# ESP32.net
KiCad netlist of a schematic drawn in EAGLE
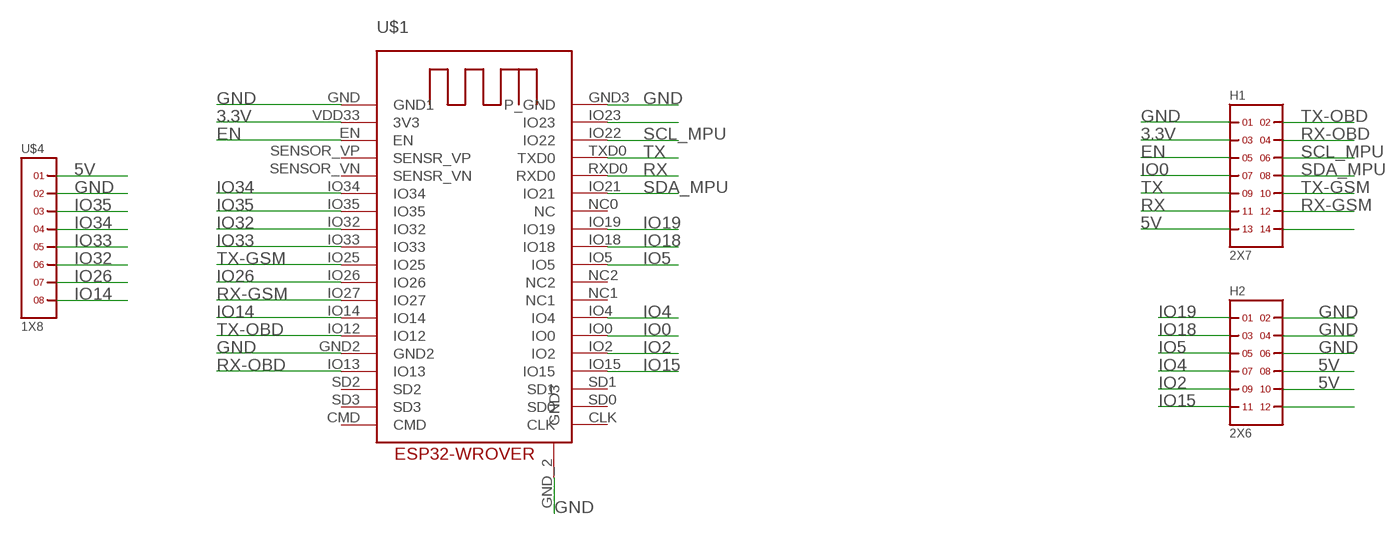
[diagram p0: schematic, sheet 1]

(export (version "E")
  (design (tool "Eeschema 10.0.6"))
  (components
    (comp (ref "H1")
      (value "2X7")
      (footprint "eagle-import:2X7")
      (libsource (lib "eagle-import") (part "2X7"))
    )
    (comp (ref "H2")
      (value "2X6")
      (footprint "eagle-import:2X6")
      (libsource (lib "eagle-import") (part "2X6"))
    )
    (comp (ref "U$1")
      (value "ESP32-WROVER")
      (footprint "eagle-import:ESP32-WROVER")
      (libsource (lib "eagle-import") (part "ESP32-WROVER"))
    )
    (comp (ref "U$4")
      (value "1X8")
      (footprint "eagle-import:1X8")
      (libsource (lib "eagle-import") (part "1X8"))
    )
  )
  (nets
    (net (code "1") (name "/3.3V") (class "Default")
      (node (ref "H1") (pin "3") (pinfunction "3_3") (pintype "bidirectional"))
      (node (ref "U$1") (pin "VDD33") (pinfunction "3V3_VDD33") (pintype "bidirectional"))
    )
    (net (code "2") (name "/5V") (class "Default")
      (node (ref "H1") (pin "13") (pinfunction "13_13") (pintype "bidirectional"))
      (node (ref "H2") (pin "10") (pinfunction "10_10") (pintype "bidirectional"))
      (node (ref "H2") (pin "8") (pinfunction "8_8") (pintype "bidirectional"))
      (node (ref "U$4") (pin "1") (pinfunction "1_1") (pintype "bidirectional"))
    )
    (net (code "3") (name "/EN") (class "Default")
      (node (ref "H1") (pin "5") (pinfunction "5_5") (pintype "bidirectional"))
      (node (ref "U$1") (pin "EN") (pinfunction "EN_EN") (pintype "bidirectional"))
    )
    (net (code "4") (name "/GND") (class "Default")
      (node (ref "H1") (pin "1") (pinfunction "1_1") (pintype "bidirectional"))
      (node (ref "H2") (pin "2") (pinfunction "2_2") (pintype "bidirectional"))
      (node (ref "H2") (pin "4") (pinfunction "4_4") (pintype "bidirectional"))
      (node (ref "H2") (pin "6") (pinfunction "6_6") (pintype "bidirectional"))
      (node (ref "U$1") (pin "GND") (pinfunction "GND1_GND") (pintype "bidirectional"))
      (node (ref "U$1") (pin "GND2") (pinfunction "GND2_GND2") (pintype "bidirectional"))
      (node (ref "U$1") (pin "GND3") (pinfunction "P_GND_GND3") (pintype "bidirectional"))
      (node (ref "U$1") (pin "GND_2") (pinfunction "GND3_GND_2") (pintype "bidirectional"))
      (node (ref "U$4") (pin "2") (pinfunction "2_2") (pintype "bidirectional"))
    )
    (net (code "5") (name "/IO0") (class "Default")
      (node (ref "H1") (pin "7") (pinfunction "7_7") (pintype "bidirectional"))
      (node (ref "U$1") (pin "IO0") (pinfunction "IO0_IO0") (pintype "bidirectional"))
    )
    (net (code "6") (name "/IO2") (class "Default")
      (node (ref "H2") (pin "9") (pinfunction "9_9") (pintype "bidirectional"))
      (node (ref "U$1") (pin "IO2") (pinfunction "IO2_IO2") (pintype "bidirectional"))
    )
    (net (code "7") (name "/IO4") (class "Default")
      (node (ref "H2") (pin "7") (pinfunction "7_7") (pintype "bidirectional"))
      (node (ref "U$1") (pin "IO4") (pinfunction "IO4_IO4") (pintype "bidirectional"))
    )
    (net (code "8") (name "/IO5") (class "Default")
      (node (ref "H2") (pin "5") (pinfunction "5_5") (pintype "bidirectional"))
      (node (ref "U$1") (pin "IO5") (pinfunction "IO5_IO5") (pintype "bidirectional"))
    )
    (net (code "9") (name "/IO14") (class "Default")
      (node (ref "U$1") (pin "IO14") (pinfunction "IO14_IO14") (pintype "bidirectional"))
      (node (ref "U$4") (pin "8") (pinfunction "8_8") (pintype "bidirectional"))
    )
    (net (code "10") (name "/IO15") (class "Default")
      (node (ref "H2") (pin "11") (pinfunction "11_11") (pintype "bidirectional"))
      (node (ref "U$1") (pin "IO15") (pinfunction "IO15_IO15") (pintype "bidirectional"))
    )
    (net (code "11") (name "/IO18") (class "Default")
      (node (ref "H2") (pin "3") (pinfunction "3_3") (pintype "bidirectional"))
      (node (ref "U$1") (pin "IO18") (pinfunction "IO18_IO18") (pintype "bidirectional"))
    )
    (net (code "12") (name "/IO19") (class "Default")
      (node (ref "H2") (pin "1") (pinfunction "1_1") (pintype "bidirectional"))
      (node (ref "U$1") (pin "IO19") (pinfunction "IO19_IO19") (pintype "bidirectional"))
    )
    (net (code "13") (name "/IO26") (class "Default")
      (node (ref "U$1") (pin "IO26") (pinfunction "IO26_IO26") (pintype "bidirectional"))
      (node (ref "U$4") (pin "7") (pinfunction "7_7") (pintype "bidirectional"))
    )
    (net (code "14") (name "/IO32") (class "Default")
      (node (ref "U$1") (pin "IO32") (pinfunction "IO32_IO32") (pintype "bidirectional"))
      (node (ref "U$4") (pin "6") (pinfunction "6_6") (pintype "bidirectional"))
    )
    (net (code "15") (name "/IO33") (class "Default")
      (node (ref "U$1") (pin "IO33") (pinfunction "IO33_IO33") (pintype "bidirectional"))
      (node (ref "U$4") (pin "5") (pinfunction "5_5") (pintype "bidirectional"))
    )
    (net (code "16") (name "/IO34") (class "Default")
      (node (ref "U$1") (pin "IO34") (pinfunction "IO34_IO34") (pintype "bidirectional"))
      (node (ref "U$4") (pin "4") (pinfunction "4_4") (pintype "bidirectional"))
    )
    (net (code "17") (name "/IO35") (class "Default")
      (node (ref "U$1") (pin "IO35") (pinfunction "IO35_IO35") (pintype "bidirectional"))
      (node (ref "U$4") (pin "3") (pinfunction "3_3") (pintype "bidirectional"))
    )
    (net (code "18") (name "/RX") (class "Default")
      (node (ref "H1") (pin "11") (pinfunction "11_11") (pintype "bidirectional"))
      (node (ref "U$1") (pin "RXD0") (pinfunction "RXD0_RXD0") (pintype "bidirectional"))
    )
    (net (code "19") (name "/RX-GSM") (class "Default")
      (node (ref "H1") (pin "12") (pinfunction "12_12") (pintype "bidirectional"))
      (node (ref "U$1") (pin "IO27") (pinfunction "IO27_IO27") (pintype "bidirectional"))
    )
    (net (code "20") (name "/RX-OBD") (class "Default")
      (node (ref "H1") (pin "4") (pinfunction "4_4") (pintype "bidirectional"))
      (node (ref "U$1") (pin "IO13") (pinfunction "IO13_IO13") (pintype "bidirectional"))
    )
    (net (code "21") (name "/SCL_MPU") (class "Default")
      (node (ref "H1") (pin "6") (pinfunction "6_6") (pintype "bidirectional"))
      (node (ref "U$1") (pin "IO22") (pinfunction "IO22_IO22") (pintype "bidirectional"))
    )
    (net (code "22") (name "/SDA_MPU") (class "Default")
      (node (ref "H1") (pin "8") (pinfunction "8_8") (pintype "bidirectional"))
      (node (ref "U$1") (pin "IO21") (pinfunction "IO21_IO21") (pintype "bidirectional"))
    )
    (net (code "23") (name "/TX") (class "Default")
      (node (ref "H1") (pin "9") (pinfunction "9_9") (pintype "bidirectional"))
      (node (ref "U$1") (pin "TXD0") (pinfunction "TXD0_TXD0") (pintype "bidirectional"))
    )
    (net (code "24") (name "/TX-GSM") (class "Default")
      (node (ref "H1") (pin "10") (pinfunction "10_10") (pintype "bidirectional"))
      (node (ref "U$1") (pin "IO25") (pinfunction "IO25_IO25") (pintype "bidirectional"))
    )
    (net (code "25") (name "/TX-OBD") (class "Default")
      (node (ref "H1") (pin "2") (pinfunction "2_2") (pintype "bidirectional"))
      (node (ref "U$1") (pin "IO12") (pinfunction "IO12_IO12") (pintype "bidirectional"))
    )
    (net (code "26") (name "unconnected-(H1-Pad14)") (class "Default")
      (node (ref "H1") (pin "14") (pinfunction "14_14") (pintype "bidirectional"))
    )
    (net (code "27") (name "unconnected-(H2-Pad12)") (class "Default")
      (node (ref "H2") (pin "12") (pinfunction "12_12") (pintype "bidirectional"))
    )
    (net (code "28") (name "unconnected-(U$1-NC-PadNC0)") (class "Default")
      (node (ref "U$1") (pin "NC0") (pinfunction "NC_NC0") (pintype "bidirectional"))
    )
    (net (code "29") (name "unconnected-(U$1-PadCLK)") (class "Default")
      (node (ref "U$1") (pin "CLK") (pinfunction "CLK_CLK") (pintype "bidirectional"))
    )
    (net (code "30") (name "unconnected-(U$1-PadCMD)") (class "Default")
      (node (ref "U$1") (pin "CMD") (pinfunction "CMD_CMD") (pintype "bidirectional"))
    )
    (net (code "31") (name "unconnected-(U$1-PadIO23)") (class "Default")
      (node (ref "U$1") (pin "IO23") (pinfunction "IO23_IO23") (pintype "bidirectional"))
    )
    (net (code "32") (name "unconnected-(U$1-PadNC1)") (class "Default")
      (node (ref "U$1") (pin "NC1") (pinfunction "NC1_NC1") (pintype "bidirectional"))
    )
    (net (code "33") (name "unconnected-(U$1-PadNC2)") (class "Default")
      (node (ref "U$1") (pin "NC2") (pinfunction "NC2_NC2") (pintype "bidirectional"))
    )
    (net (code "34") (name "unconnected-(U$1-PadSD0)") (class "Default")
      (node (ref "U$1") (pin "SD0") (pinfunction "SD0_SD0") (pintype "bidirectional"))
    )
    (net (code "35") (name "unconnected-(U$1-PadSD1)") (class "Default")
      (node (ref "U$1") (pin "SD1") (pinfunction "SD1_SD1") (pintype "bidirectional"))
    )
    (net (code "36") (name "unconnected-(U$1-PadSD2)") (class "Default")
      (node (ref "U$1") (pin "SD2") (pinfunction "SD2_SD2") (pintype "bidirectional"))
    )
    (net (code "37") (name "unconnected-(U$1-PadSD3)") (class "Default")
      (node (ref "U$1") (pin "SD3") (pinfunction "SD3_SD3") (pintype "bidirectional"))
    )
    (net (code "38") (name "unconnected-(U$1-SENSR_VN-PadSENSOR_VN)") (class "Default")
      (node (ref "U$1") (pin "SENSOR_VN") (pinfunction "SENSR_VN_SENSOR_VN") (pintype "bidirectional"))
    )
    (net (code "39") (name "unconnected-(U$1-SENSR_VP-PadSENSOR_VP)") (class "Default")
      (node (ref "U$1") (pin "SENSOR_VP") (pinfunction "SENSR_VP_SENSOR_VP") (pintype "bidirectional"))
    )
  )
)
